# nutnhanguyen_ly.net
KiCad netlist of a schematic drawn in Altium Designer
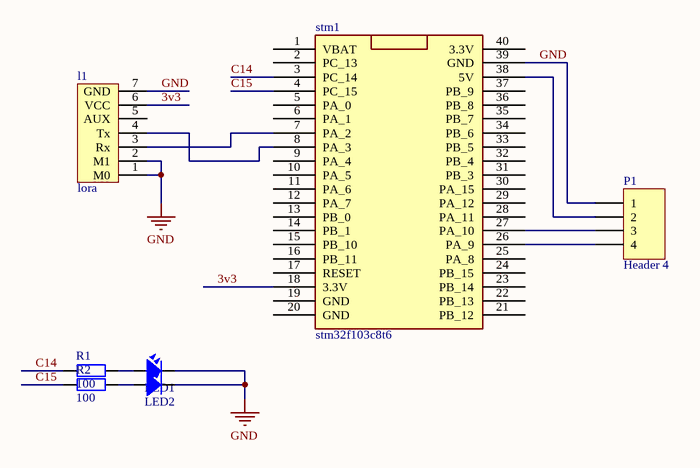
[diagram p0: nutnhanguyen ly.SchDoc]

(export (version "E")
  (design (tool "Eeschema 10.0.6"))
  (components
    (comp (ref "l1")
      (value "lora")
      (footprint "lora sx1278")
      (libsource (lib "link kien_thien") (part "lora SX1278"))
    )
    (comp (ref "LED1")
      (value "LED")
      (footprint "LED-5-RED")
      (description "LED Single colour Green and Red")
      (libsource (lib "LIBRARY1") (part "LED"))
    )
    (comp (ref "LED2")
      (value "LED")
      (footprint "LED-5-RED")
      (description "LED Single colour Green and Red")
      (libsource (lib "LIBRARY1") (part "LED"))
    )
    (comp (ref "P1")
      (value "Header 4")
      (footprint "HDR1X4")
      (description "Header, 4-Pin")
      (fields (field (name "PUBLISHER") "Altium Limited"))
      (libsource (lib "My Library") (part "Header 4"))
    )
    (comp (ref "R1")
      (value "100")
      (footprint "R1/4W")
      (description "Resistor 1/4W")
      (libsource (lib "My Library") (part "R1/4W"))
    )
    (comp (ref "R2")
      (value "100")
      (footprint "R1/4W")
      (description "Resistor 1/4W")
      (libsource (lib "My Library") (part "R1/4W"))
    )
    (comp (ref "stm1")
      (value "stm32f103c8t6")
      (footprint "40chan")
      (libsource (lib "link kien_thien") (part "stm32f103c8t6"))
    )
  )
  (nets
    (net (code "1") (name "/3v3") (class "Default")
      (node (ref "l1") (pin "6") (pinfunction "VCC_6") (pintype "passive"))
      (node (ref "stm1") (pin "18") (pinfunction "3.3V_18") (pintype "passive"))
    )
    (net (code "2") (name "/C14") (class "Default")
      (node (ref "R1") (pin "1") (pinfunction "1_1") (pintype "passive"))
      (node (ref "stm1") (pin "3") (pinfunction "PC_14_3") (pintype "passive"))
    )
    (net (code "3") (name "/C15") (class "Default")
      (node (ref "R2") (pin "1") (pinfunction "1_1") (pintype "passive"))
      (node (ref "stm1") (pin "4") (pinfunction "PC_15_4") (pintype "passive"))
    )
    (net (code "4") (name "GND") (class "Default")
      (node (ref "LED1") (pin "2") (pinfunction "2_2") (pintype "passive"))
      (node (ref "LED2") (pin "2") (pinfunction "2_2") (pintype "passive"))
      (node (ref "P1") (pin "1") (pinfunction "1_1") (pintype "passive"))
      (node (ref "l1") (pin "1") (pinfunction "M0_1") (pintype "passive"))
      (node (ref "l1") (pin "2") (pinfunction "M1_2") (pintype "passive"))
      (node (ref "l1") (pin "7") (pinfunction "GND_7") (pintype "passive"))
      (node (ref "stm1") (pin "39") (pinfunction "GND_39") (pintype "passive"))
    )
    (net (code "5") (name "Net-(LED1-Pad1)") (class "Default")
      (node (ref "LED1") (pin "1") (pinfunction "1_1") (pintype "passive"))
      (node (ref "R1") (pin "2") (pinfunction "2_2") (pintype "passive"))
    )
    (net (code "6") (name "Net-(LED2-Pad1)") (class "Default")
      (node (ref "LED2") (pin "1") (pinfunction "1_1") (pintype "passive"))
      (node (ref "R2") (pin "2") (pinfunction "2_2") (pintype "passive"))
    )
    (net (code "7") (name "Net-(l1-Rx)") (class "Default")
      (node (ref "l1") (pin "3") (pinfunction "Rx_3") (pintype "passive"))
      (node (ref "stm1") (pin "7") (pinfunction "PA_2_7") (pintype "passive"))
    )
    (net (code "8") (name "Net-(l1-Tx)") (class "Default")
      (node (ref "l1") (pin "4") (pinfunction "Tx_4") (pintype "passive"))
      (node (ref "stm1") (pin "8") (pinfunction "PA_3_8") (pintype "passive"))
    )
    (net (code "9") (name "Net-(stm1-5V)") (class "Default")
      (node (ref "P1") (pin "2") (pinfunction "2_2") (pintype "passive"))
      (node (ref "stm1") (pin "38") (pinfunction "5V_38") (pintype "passive"))
    )
    (net (code "10") (name "Net-(stm1-PA_9)") (class "Default")
      (node (ref "P1") (pin "4") (pinfunction "4_4") (pintype "passive"))
      (node (ref "stm1") (pin "26") (pinfunction "PA_9_26") (pintype "passive"))
    )
    (net (code "11") (name "Net-(stm1-PA_10)") (class "Default")
      (node (ref "P1") (pin "3") (pinfunction "3_3") (pintype "passive"))
      (node (ref "stm1") (pin "27") (pinfunction "PA_10_27") (pintype "passive"))
    )
    (net (code "12") (name "unconnected-(l1-AUX-Pad5)") (class "Default")
      (node (ref "l1") (pin "5") (pinfunction "AUX_5") (pintype "passive"))
    )
    (net (code "13") (name "unconnected-(stm1-3.3V-Pad40)") (class "Default")
      (node (ref "stm1") (pin "40") (pinfunction "3.3V_40") (pintype "passive"))
    )
    (net (code "14") (name "unconnected-(stm1-GND-Pad19)") (class "Default")
      (node (ref "stm1") (pin "19") (pinfunction "GND_19") (pintype "passive"))
    )
    (net (code "15") (name "unconnected-(stm1-GND-Pad20)") (class "Default")
      (node (ref "stm1") (pin "20") (pinfunction "GND_20") (pintype "passive"))
    )
    (net (code "16") (name "unconnected-(stm1-PA_0-Pad5)") (class "Default")
      (node (ref "stm1") (pin "5") (pinfunction "PA_0_5") (pintype "passive"))
    )
    (net (code "17") (name "unconnected-(stm1-PA_1-Pad6)") (class "Default")
      (node (ref "stm1") (pin "6") (pinfunction "PA_1_6") (pintype "passive"))
    )
    (net (code "18") (name "unconnected-(stm1-PA_4-Pad9)") (class "Default")
      (node (ref "stm1") (pin "9") (pinfunction "PA_4_9") (pintype "passive"))
    )
    (net (code "19") (name "unconnected-(stm1-PA_5-Pad10)") (class "Default")
      (node (ref "stm1") (pin "10") (pinfunction "PA_5_10") (pintype "passive"))
    )
    (net (code "20") (name "unconnected-(stm1-PA_6-Pad11)") (class "Default")
      (node (ref "stm1") (pin "11") (pinfunction "PA_6_11") (pintype "passive"))
    )
    (net (code "21") (name "unconnected-(stm1-PA_7-Pad12)") (class "Default")
      (node (ref "stm1") (pin "12") (pinfunction "PA_7_12") (pintype "passive"))
    )
    (net (code "22") (name "unconnected-(stm1-PA_8-Pad25)") (class "Default")
      (node (ref "stm1") (pin "25") (pinfunction "PA_8_25") (pintype "passive"))
    )
    (net (code "23") (name "unconnected-(stm1-PA_11-Pad28)") (class "Default")
      (node (ref "stm1") (pin "28") (pinfunction "PA_11_28") (pintype "passive"))
    )
    (net (code "24") (name "unconnected-(stm1-PA_12-Pad29)") (class "Default")
      (node (ref "stm1") (pin "29") (pinfunction "PA_12_29") (pintype "passive"))
    )
    (net (code "25") (name "unconnected-(stm1-PA_15-Pad30)") (class "Default")
      (node (ref "stm1") (pin "30") (pinfunction "PA_15_30") (pintype "passive"))
    )
    (net (code "26") (name "unconnected-(stm1-PB_0-Pad13)") (class "Default")
      (node (ref "stm1") (pin "13") (pinfunction "PB_0_13") (pintype "passive"))
    )
    (net (code "27") (name "unconnected-(stm1-PB_1-Pad14)") (class "Default")
      (node (ref "stm1") (pin "14") (pinfunction "PB_1_14") (pintype "passive"))
    )
    (net (code "28") (name "unconnected-(stm1-PB_3-Pad31)") (class "Default")
      (node (ref "stm1") (pin "31") (pinfunction "PB_3_31") (pintype "passive"))
    )
    (net (code "29") (name "unconnected-(stm1-PB_4-Pad32)") (class "Default")
      (node (ref "stm1") (pin "32") (pinfunction "PB_4_32") (pintype "passive"))
    )
    (net (code "30") (name "unconnected-(stm1-PB_5-Pad33)") (class "Default")
      (node (ref "stm1") (pin "33") (pinfunction "PB_5_33") (pintype "passive"))
    )
    (net (code "31") (name "unconnected-(stm1-PB_6-Pad34)") (class "Default")
      (node (ref "stm1") (pin "34") (pinfunction "PB_6_34") (pintype "passive"))
    )
    (net (code "32") (name "unconnected-(stm1-PB_7-Pad35)") (class "Default")
      (node (ref "stm1") (pin "35") (pinfunction "PB_7_35") (pintype "passive"))
    )
    (net (code "33") (name "unconnected-(stm1-PB_8-Pad36)") (class "Default")
      (node (ref "stm1") (pin "36") (pinfunction "PB_8_36") (pintype "passive"))
    )
    (net (code "34") (name "unconnected-(stm1-PB_9-Pad37)") (class "Default")
      (node (ref "stm1") (pin "37") (pinfunction "PB_9_37") (pintype "passive"))
    )
    (net (code "35") (name "unconnected-(stm1-PB_10-Pad15)") (class "Default")
      (node (ref "stm1") (pin "15") (pinfunction "PB_10_15") (pintype "passive"))
    )
    (net (code "36") (name "unconnected-(stm1-PB_11-Pad16)") (class "Default")
      (node (ref "stm1") (pin "16") (pinfunction "PB_11_16") (pintype "passive"))
    )
    (net (code "37") (name "unconnected-(stm1-PB_12-Pad21)") (class "Default")
      (node (ref "stm1") (pin "21") (pinfunction "PB_12_21") (pintype "passive"))
    )
    (net (code "38") (name "unconnected-(stm1-PB_13-Pad22)") (class "Default")
      (node (ref "stm1") (pin "22") (pinfunction "PB_13_22") (pintype "passive"))
    )
    (net (code "39") (name "unconnected-(stm1-PB_14-Pad23)") (class "Default")
      (node (ref "stm1") (pin "23") (pinfunction "PB_14_23") (pintype "passive"))
    )
    (net (code "40") (name "unconnected-(stm1-PB_15-Pad24)") (class "Default")
      (node (ref "stm1") (pin "24") (pinfunction "PB_15_24") (pintype "passive"))
    )
    (net (code "41") (name "unconnected-(stm1-PC_13-Pad2)") (class "Default")
      (node (ref "stm1") (pin "2") (pinfunction "PC_13_2") (pintype "passive"))
    )
    (net (code "42") (name "unconnected-(stm1-RESET-Pad17)") (class "Default")
      (node (ref "stm1") (pin "17") (pinfunction "RESET_17") (pintype "passive"))
    )
    (net (code "43") (name "unconnected-(stm1-VBAT-Pad1)") (class "Default")
      (node (ref "stm1") (pin "1") (pinfunction "VBAT_1") (pintype "passive"))
    )
  )
)
